# Uc_Ticketing_Master.net
KiCad netlist of a schematic drawn in Altium Designer
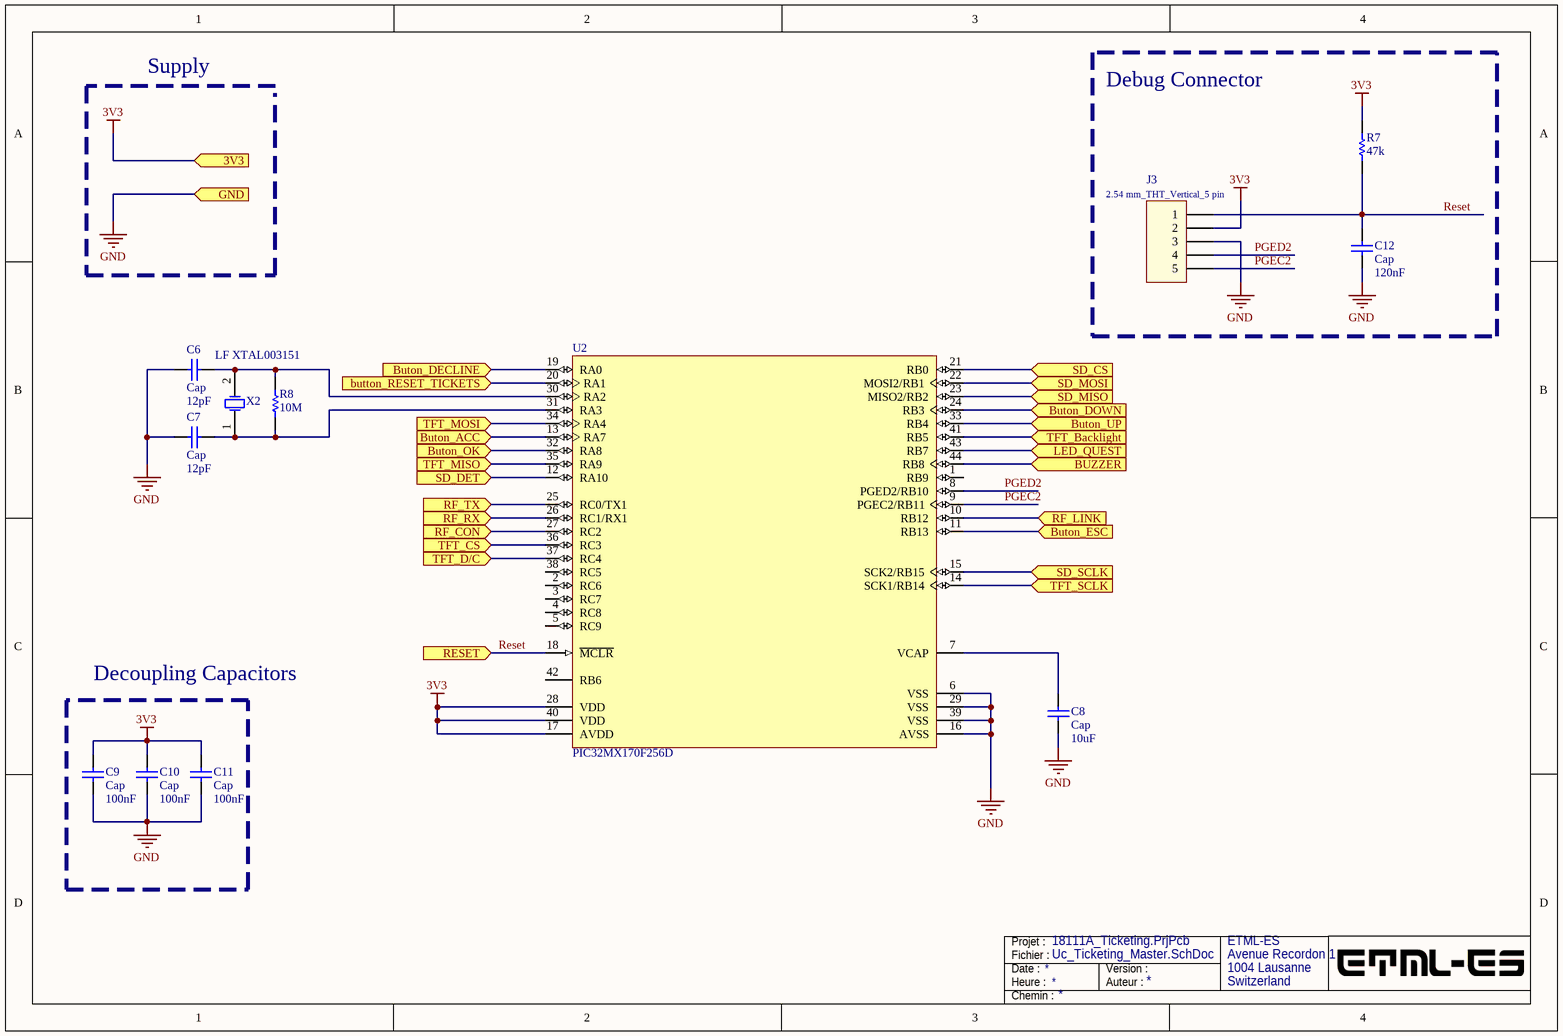
[diagram p0: Uc_Ticketing_Master.SchDoc]

(export (version "E")
  (design (tool "Eeschema 10.0.6"))
  (components
    (comp (ref "C6")
      (value "Cap")
      (footprint "6-0805_N")
      (description "Capacitor")
      (fields (field (name "ALTIUM_VALUE") "12pF") (field (name "PUBLISHER") "Altium Limited"))
      (libsource (lib "Miscellaneous Devices") (part "Cap"))
    )
    (comp (ref "C7")
      (value "Cap")
      (footprint "6-0805_N")
      (description "Capacitor")
      (fields (field (name "ALTIUM_VALUE") "12pF") (field (name "PUBLISHER") "Altium Limited"))
      (libsource (lib "Miscellaneous Devices") (part "Cap"))
    )
    (comp (ref "C8")
      (value "Cap")
      (footprint "6-0805_N")
      (description "Capacitor")
      (fields (field (name "ALTIUM_VALUE") "10uF") (field (name "PUBLISHER") "Altium Limited"))
      (libsource (lib "Miscellaneous Devices") (part "Cap"))
    )
    (comp (ref "C9")
      (value "Cap")
      (footprint "6-0805_N")
      (description "Capacitor")
      (fields (field (name "ALTIUM_VALUE") "100nF") (field (name "PUBLISHER") "Altium Limited"))
      (libsource (lib "Miscellaneous Devices") (part "Cap"))
    )
    (comp (ref "C10")
      (value "Cap")
      (footprint "6-0805_N")
      (description "Capacitor")
      (fields (field (name "ALTIUM_VALUE") "100nF") (field (name "PUBLISHER") "Altium Limited"))
      (libsource (lib "Miscellaneous Devices") (part "Cap"))
    )
    (comp (ref "C11")
      (value "Cap")
      (footprint "6-0805_N")
      (description "Capacitor")
      (fields (field (name "ALTIUM_VALUE") "100nF") (field (name "PUBLISHER") "Altium Limited"))
      (libsource (lib "Miscellaneous Devices") (part "Cap"))
    )
    (comp (ref "C12")
      (value "Cap")
      (footprint "6-0805_N")
      (description "Capacitor")
      (fields (field (name "ALTIUM_VALUE") "120nF") (field (name "PUBLISHER") "Altium Limited"))
      (libsource (lib "Miscellaneous Devices") (part "Cap"))
    )
    (comp (ref "J3")
      (value "2.54 mm_THT_Vertical_5 pin")
      (footprint "61300511121")
      (description "Pin Header WR-PHD, pitch 2.54 mm, THT, Vertical, single row, 5 pin")
      (fields (field (name "PART NUMBER") "61300511121") (field (name "PUBLISHER") "Wurth Elektronik"))
      (libsource (lib "ALTIUM-PHD_2_54_THT_PIN_HEADER_6130XX11121-rev18a") (part "61300511121"))
    )
    (comp (ref "R7")
      (value "47k")
      (footprint "RESC0805(2012)_L")
      (description "100K 0.125W 5% 0805 (2012 Metric)  SMD")
      (fields (field (name "TOLERANCE") "5 %") (field (name "POWER") "0.125 W"))
      (libsource (lib "Altium Content Vault") (part "CMP-1013-00122-1"))
    )
    (comp (ref "R8")
      (value "10M")
      (footprint "RESC0805(2012)_L")
      (description "100K 0.125W 5% 0805 (2012 Metric)  SMD")
      (fields (field (name "TOLERANCE") "5 %") (field (name "POWER") "0.125 W"))
      (libsource (lib "Altium Content Vault") (part "CMP-1013-00122-1"))
    )
    (comp (ref "U2")
      (value "PIC32MX170F256D")
      (footprint "MCHP-TQFP-PT44_N")
      (libsource (lib "PIC32MX170F256D") (part "MCHP-PIC32MX2XXFXXXD-TQFP-44"))
    )
    (comp (ref "X2")
      (value "LF XTAL003151")
      (footprint "ECS-80-18-5PX-TR_V")
      (description "Low Profile Quartz Crystal, 8.0 MHz, 2-Pin SMD, RoHS, Tape and Reel")
      (fields (field (name "TOLERANCE") "30PPM") (field (name "MANUFACTURER") "ECS"))
      (libsource (lib "Altium Content Vault") (part "XTAL_1-2-2"))
    )
  )
  (nets
    (net (code "1") (name "/BUZZER") (class "Default")
      (node (ref "U2") (pin "44") (pinfunction "RB8_44") (pintype "bidirectional"))
    )
    (net (code "2") (name "/Buton_ACC") (class "Default")
      (node (ref "U2") (pin "13") (pinfunction "RA7_13") (pintype "bidirectional"))
    )
    (net (code "3") (name "/Buton_DECLINE") (class "Default")
      (node (ref "U2") (pin "19") (pinfunction "RA0_19") (pintype "bidirectional"))
    )
    (net (code "4") (name "/Buton_DOWN") (class "Default")
      (node (ref "U2") (pin "24") (pinfunction "RB3_24") (pintype "bidirectional"))
    )
    (net (code "5") (name "/Buton_ESC") (class "Default")
      (node (ref "U2") (pin "11") (pinfunction "RB13_11") (pintype "bidirectional"))
    )
    (net (code "6") (name "/Buton_OK") (class "Default")
      (node (ref "U2") (pin "32") (pinfunction "RA8_32") (pintype "bidirectional"))
    )
    (net (code "7") (name "/Buton_UP") (class "Default")
      (node (ref "U2") (pin "33") (pinfunction "RB4_33") (pintype "bidirectional"))
    )
    (net (code "8") (name "/LED_QUEST") (class "Default")
      (node (ref "U2") (pin "43") (pinfunction "RB7_43") (pintype "bidirectional"))
    )
    (net (code "9") (name "/PGEC2") (class "Default")
      (node (ref "J3") (pin "5") (pinfunction "5_5") (pintype "passive"))
      (node (ref "U2") (pin "9") (pinfunction "PGEC2/RB11_9") (pintype "bidirectional"))
    )
    (net (code "10") (name "/PGED2") (class "Default")
      (node (ref "J3") (pin "4") (pinfunction "4_4") (pintype "passive"))
      (node (ref "U2") (pin "8") (pinfunction "PGED2/RB10_8") (pintype "bidirectional"))
    )
    (net (code "11") (name "/RF_CON") (class "Default")
      (node (ref "U2") (pin "27") (pinfunction "RC2_27") (pintype "bidirectional"))
    )
    (net (code "12") (name "/RF_LINK") (class "Default")
      (node (ref "U2") (pin "10") (pinfunction "RB12_10") (pintype "bidirectional"))
    )
    (net (code "13") (name "/RF_RX") (class "Default")
      (node (ref "U2") (pin "26") (pinfunction "RC1/RX1_26") (pintype "bidirectional"))
    )
    (net (code "14") (name "/RF_TX") (class "Default")
      (node (ref "U2") (pin "25") (pinfunction "RC0/TX1_25") (pintype "bidirectional"))
    )
    (net (code "15") (name "/Reset") (class "Default")
      (node (ref "C12") (pin "2") (pinfunction "2_2") (pintype "passive"))
      (node (ref "J3") (pin "1") (pinfunction "1_1") (pintype "passive"))
      (node (ref "R7") (pin "2") (pinfunction "2_2") (pintype "passive"))
      (node (ref "U2") (pin "18") (pinfunction "~{MCLR}_18") (pintype "input"))
    )
    (net (code "16") (name "/SD_CS") (class "Default")
      (node (ref "U2") (pin "21") (pinfunction "RB0_21") (pintype "bidirectional"))
    )
    (net (code "17") (name "/SD_DET") (class "Default")
      (node (ref "U2") (pin "12") (pinfunction "RA10_12") (pintype "bidirectional"))
    )
    (net (code "18") (name "/SD_MISO") (class "Default")
      (node (ref "U2") (pin "23") (pinfunction "MISO2/RB2_23") (pintype "bidirectional"))
    )
    (net (code "19") (name "/SD_MOSI") (class "Default")
      (node (ref "U2") (pin "22") (pinfunction "MOSI2/RB1_22") (pintype "bidirectional"))
    )
    (net (code "20") (name "/SD_SCLK") (class "Default")
      (node (ref "U2") (pin "15") (pinfunction "SCK2/RB15_15") (pintype "bidirectional"))
    )
    (net (code "21") (name "/TFT_Backlight") (class "Default")
      (node (ref "U2") (pin "41") (pinfunction "RB5_41") (pintype "bidirectional"))
    )
    (net (code "22") (name "/TFT_CS") (class "Default")
      (node (ref "U2") (pin "36") (pinfunction "RC3_36") (pintype "bidirectional"))
    )
    (net (code "23") (name "/TFT_D{slash}C") (class "Default")
      (node (ref "U2") (pin "37") (pinfunction "RC4_37") (pintype "bidirectional"))
    )
    (net (code "24") (name "/TFT_MISO") (class "Default")
      (node (ref "U2") (pin "35") (pinfunction "RA9_35") (pintype "bidirectional"))
    )
    (net (code "25") (name "/TFT_MOSI") (class "Default")
      (node (ref "U2") (pin "34") (pinfunction "RA4_34") (pintype "bidirectional"))
    )
    (net (code "26") (name "/TFT_SCLK") (class "Default")
      (node (ref "U2") (pin "14") (pinfunction "SCK1/RB14_14") (pintype "bidirectional"))
    )
    (net (code "27") (name "/button_RESET_TICKETS") (class "Default")
      (node (ref "U2") (pin "20") (pinfunction "RA1_20") (pintype "bidirectional"))
    )
    (net (code "28") (name "3V3") (class "Default")
      (node (ref "C10") (pin "2") (pinfunction "2_2") (pintype "passive"))
      (node (ref "C11") (pin "2") (pinfunction "2_2") (pintype "passive"))
      (node (ref "C9") (pin "2") (pinfunction "2_2") (pintype "passive"))
      (node (ref "J3") (pin "2") (pinfunction "2_2") (pintype "passive"))
      (node (ref "R7") (pin "1") (pinfunction "1_1") (pintype "passive"))
      (node (ref "U2") (pin "17") (pinfunction "AVDD_17") (pintype "power_in"))
      (node (ref "U2") (pin "28") (pinfunction "VDD_28") (pintype "power_in"))
      (node (ref "U2") (pin "40") (pinfunction "VDD_40") (pintype "power_in"))
    )
    (net (code "29") (name "GND") (class "Default")
      (node (ref "C10") (pin "1") (pinfunction "1_1") (pintype "passive"))
      (node (ref "C11") (pin "1") (pinfunction "1_1") (pintype "passive"))
      (node (ref "C12") (pin "1") (pinfunction "1_1") (pintype "passive"))
      (node (ref "C6") (pin "1") (pinfunction "1_1") (pintype "passive"))
      (node (ref "C7") (pin "2") (pinfunction "2_2") (pintype "passive"))
      (node (ref "C8") (pin "1") (pinfunction "1_1") (pintype "passive"))
      (node (ref "C9") (pin "1") (pinfunction "1_1") (pintype "passive"))
      (node (ref "J3") (pin "3") (pinfunction "3_3") (pintype "passive"))
      (node (ref "U2") (pin "16") (pinfunction "AVSS_16") (pintype "power_in"))
      (node (ref "U2") (pin "29") (pinfunction "VSS_29") (pintype "power_in"))
      (node (ref "U2") (pin "39") (pinfunction "VSS_39") (pintype "power_in"))
      (node (ref "U2") (pin "6") (pinfunction "VSS_6") (pintype "power_in"))
    )
    (net (code "30") (name "Net-(U2-RA2)") (class "Default")
      (node (ref "C6") (pin "2") (pinfunction "2_2") (pintype "passive"))
      (node (ref "R8") (pin "2") (pinfunction "2_2") (pintype "passive"))
      (node (ref "U2") (pin "30") (pinfunction "RA2_30") (pintype "bidirectional"))
      (node (ref "X2") (pin "2") (pinfunction "X2_2") (pintype "passive"))
    )
    (net (code "31") (name "Net-(U2-RA3)") (class "Default")
      (node (ref "C7") (pin "1") (pinfunction "1_1") (pintype "passive"))
      (node (ref "R8") (pin "1") (pinfunction "1_1") (pintype "passive"))
      (node (ref "U2") (pin "31") (pinfunction "RA3_31") (pintype "bidirectional"))
      (node (ref "X2") (pin "1") (pinfunction "X1_1") (pintype "passive"))
    )
    (net (code "32") (name "Net-(U2-VCAP)") (class "Default")
      (node (ref "C8") (pin "2") (pinfunction "2_2") (pintype "passive"))
      (node (ref "U2") (pin "7") (pinfunction "VCAP_7") (pintype "passive"))
    )
    (net (code "33") (name "unconnected-(U2-RB6-Pad42)") (class "Default")
      (node (ref "U2") (pin "42") (pinfunction "RB6_42") (pintype "power_in"))
    )
    (net (code "34") (name "unconnected-(U2-RB9-Pad1)") (class "Default")
      (node (ref "U2") (pin "1") (pinfunction "RB9_1") (pintype "bidirectional"))
    )
    (net (code "35") (name "unconnected-(U2-RC5-Pad38)") (class "Default")
      (node (ref "U2") (pin "38") (pinfunction "RC5_38") (pintype "bidirectional"))
    )
    (net (code "36") (name "unconnected-(U2-RC6-Pad2)") (class "Default")
      (node (ref "U2") (pin "2") (pinfunction "RC6_2") (pintype "bidirectional"))
    )
    (net (code "37") (name "unconnected-(U2-RC7-Pad3)") (class "Default")
      (node (ref "U2") (pin "3") (pinfunction "RC7_3") (pintype "bidirectional"))
    )
    (net (code "38") (name "unconnected-(U2-RC8-Pad4)") (class "Default")
      (node (ref "U2") (pin "4") (pinfunction "RC8_4") (pintype "bidirectional"))
    )
    (net (code "39") (name "unconnected-(U2-RC9-Pad5)") (class "Default")
      (node (ref "U2") (pin "5") (pinfunction "RC9_5") (pintype "bidirectional"))
    )
  )
)
